# Ref_DAC.net
KiCad netlist of a schematic drawn in Altium Designer
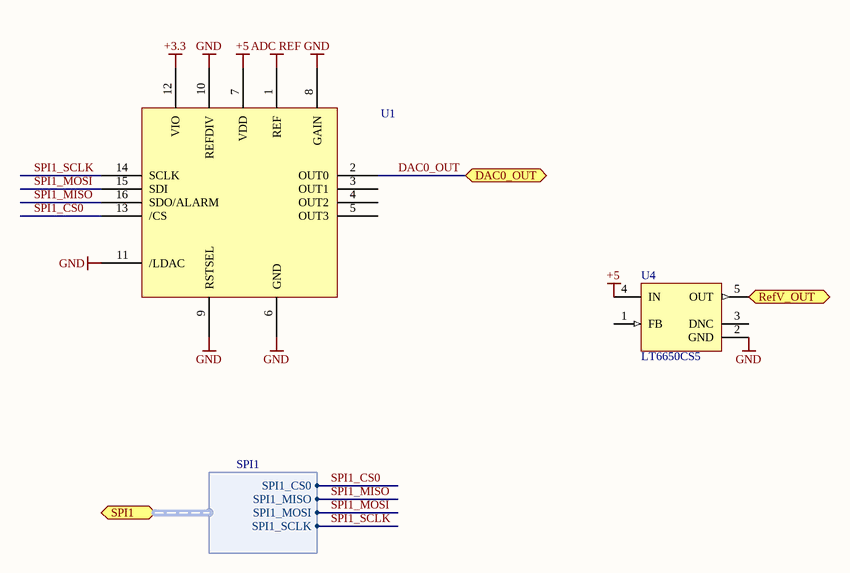
[diagram p0: Ref_DAC.SchDoc]

(export (version "E")
  (design (tool "Eeschema 10.0.6"))
  (components
    (comp (ref "U1")
      (value "DAC80504")
      (footprint "DAC80504")
      (libsource (lib "ZLS_Schematic_lib") (part "DAC80504"))
    )
    (comp (ref "U4")
      (value "LT6650CS5")
      (footprint "LT-S5-5-TSOT-23_N")
      (libsource (lib "Altium Content Vault") (part "LT-LT6650-S5-5"))
    )
  )
  (nets
    (net (code "2") (name "+3.3") (class "Default")
      (node (ref "U1") (pin "12") (pinfunction "VIO_12") (pintype "passive"))
    )
    (net (code "3") (name "+5") (class "Default")
      (node (ref "U1") (pin "7") (pinfunction "VDD_7") (pintype "passive"))
      (node (ref "U4") (pin "4") (pinfunction "IN_4") (pintype "power_in"))
    )
    (net (code "4") (name "/DAC0_OUT") (class "Default")
      (node (ref "U1") (pin "2") (pinfunction "OUT0_2") (pintype "passive"))
    )
    (net (code "5") (name "/RefV_OUT") (class "Default")
      (node (ref "U4") (pin "5") (pinfunction "OUT_5") (pintype "output"))
    )
    (net (code "6") (name "/SPI1_CS0") (class "Default")
      (node (ref "U1") (pin "13") (pinfunction "/CS_13") (pintype "passive"))
    )
    (net (code "7") (name "/SPI1_MISO") (class "Default")
      (node (ref "U1") (pin "16") (pinfunction "SDO/ALARM_16") (pintype "passive"))
    )
    (net (code "8") (name "/SPI1_MOSI") (class "Default")
      (node (ref "U1") (pin "15") (pinfunction "SDI_15") (pintype "passive"))
    )
    (net (code "9") (name "/SPI1_SCLK") (class "Default")
      (node (ref "U1") (pin "14") (pinfunction "SCLK_14") (pintype "passive"))
    )
    (net (code "11") (name "ADC REF") (class "Default")
      (node (ref "U1") (pin "1") (pinfunction "REF_1") (pintype "passive"))
    )
    (net (code "12") (name "GND") (class "Default")
      (node (ref "U1") (pin "10") (pinfunction "REFDIV_10") (pintype "passive"))
      (node (ref "U1") (pin "11") (pinfunction "/LDAC_11") (pintype "passive"))
      (node (ref "U1") (pin "6") (pinfunction "GND_6") (pintype "passive"))
      (node (ref "U1") (pin "8") (pinfunction "GAIN_8") (pintype "passive"))
      (node (ref "U1") (pin "9") (pinfunction "RSTSEL_9") (pintype "passive"))
      (node (ref "U4") (pin "2") (pinfunction "GND_2") (pintype "power_in"))
    )
    (net (code "13") (name "unconnected-(U1-OUT1-Pad3)") (class "Default")
      (node (ref "U1") (pin "3") (pinfunction "OUT1_3") (pintype "passive"))
    )
    (net (code "14") (name "unconnected-(U1-OUT2-Pad4)") (class "Default")
      (node (ref "U1") (pin "4") (pinfunction "OUT2_4") (pintype "passive"))
    )
    (net (code "15") (name "unconnected-(U1-OUT3-Pad5)") (class "Default")
      (node (ref "U1") (pin "5") (pinfunction "OUT3_5") (pintype "passive"))
    )
    (net (code "16") (name "unconnected-(U4-DNC-Pad3)") (class "Default")
      (node (ref "U4") (pin "3") (pinfunction "DNC_3") (pintype "passive"))
    )
    (net (code "17") (name "unconnected-(U4-FB-Pad1)") (class "Default")
      (node (ref "U4") (pin "1") (pinfunction "FB_1") (pintype "input"))
    )
  )
)
